# LilyPad_Arduino_SimpleSnap.net
KiCad netlist of a schematic drawn in EAGLE
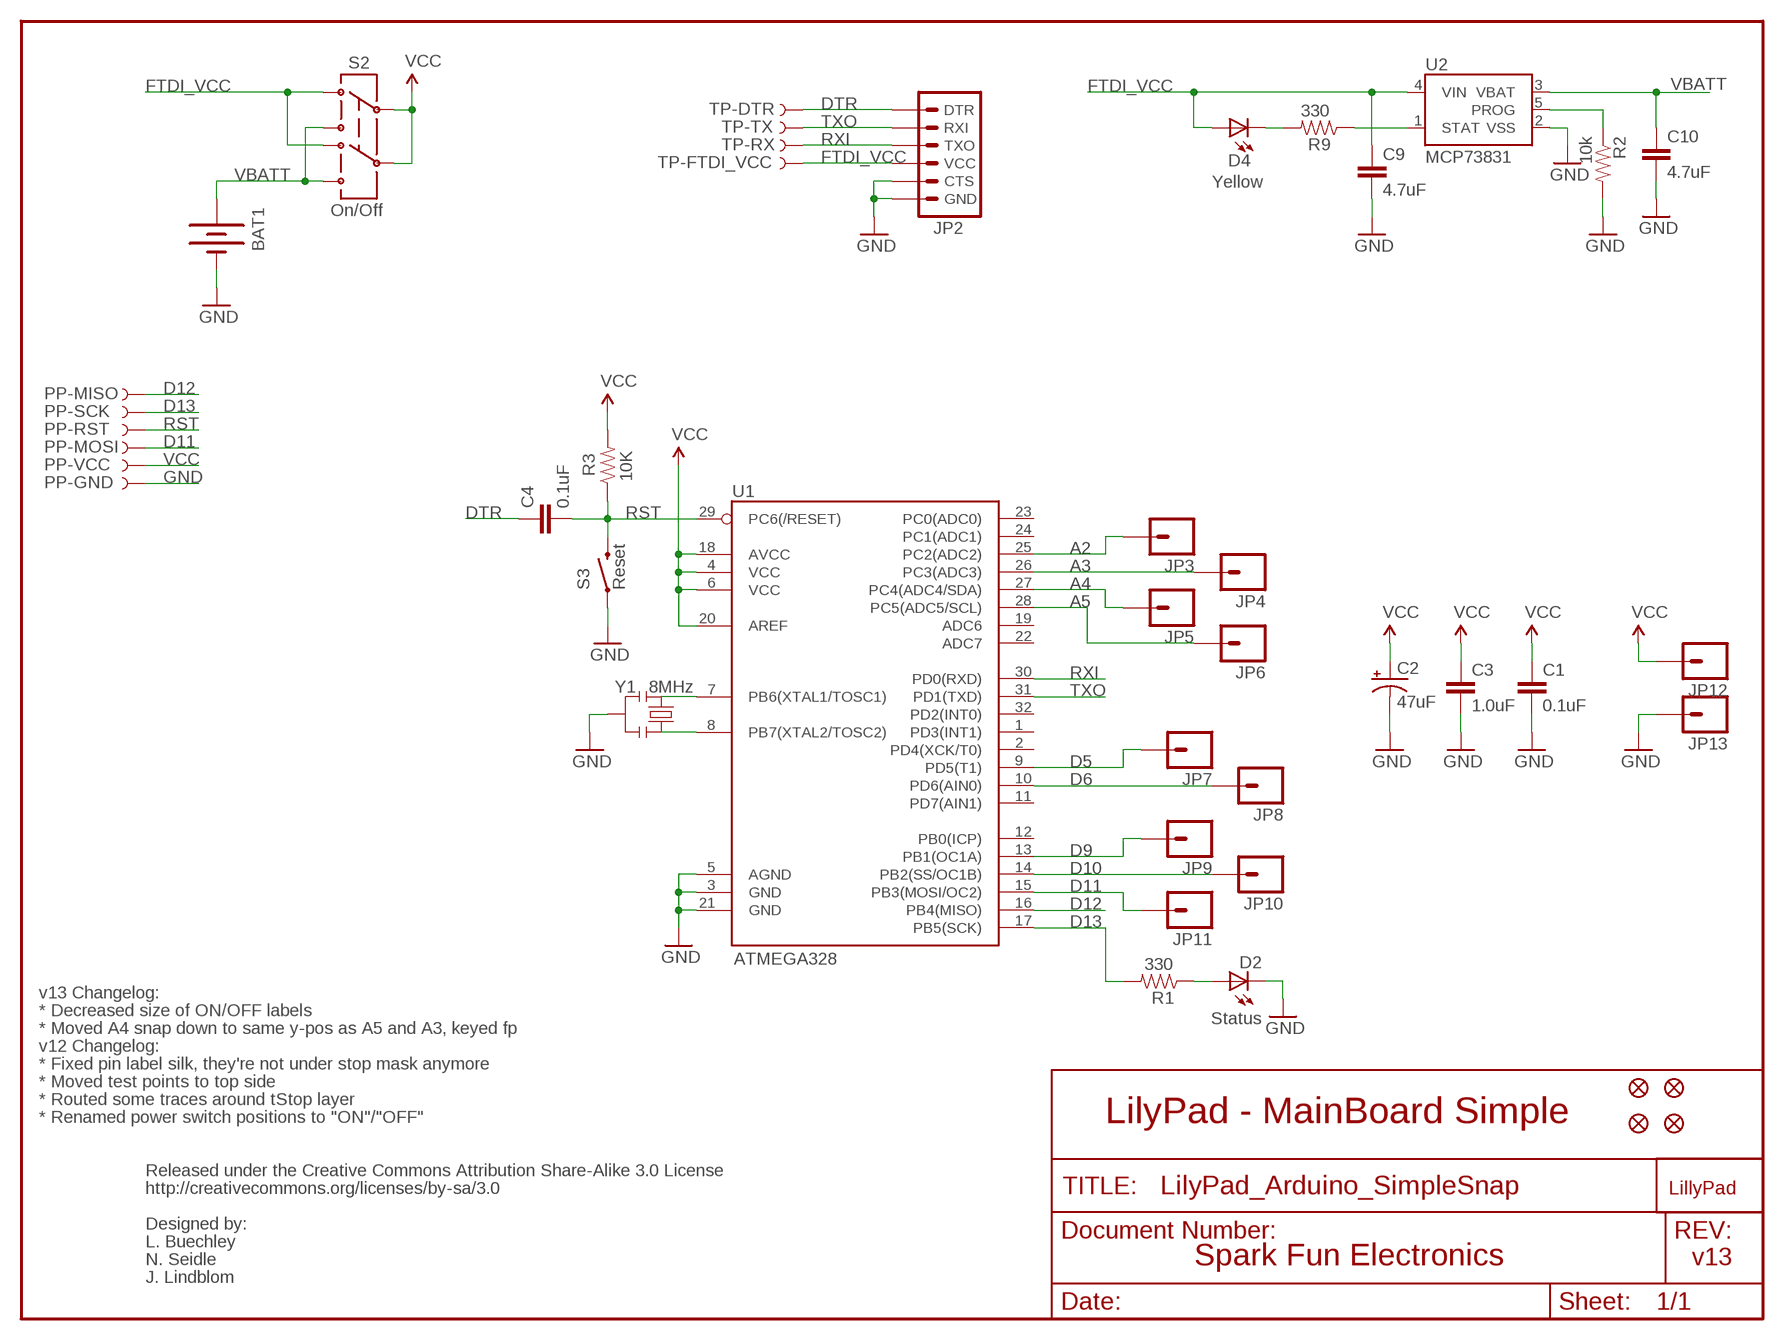
[diagram p0: schematic, sheet 1]

(export (version "E")
  (design (tool "Eeschema 10.0.6"))
  (components
    (comp (ref "BAT1")
      (value "BATTERY110-TABS")
      (footprint "eagle-import:LIPO-110-TABS")
      (libsource (lib "eagle-import") (part "BATTERY110-TABS"))
    )
    (comp (ref "C1")
      (value "0.1uF")
      (footprint "eagle-import:0402-CAP")
      (libsource (lib "eagle-import") (part "CAP0402-CAP"))
    )
    (comp (ref "C2")
      (value "47uF")
      (footprint "eagle-import:EIA3528")
      (libsource (lib "eagle-import") (part "CAP_POL3528"))
    )
    (comp (ref "C3")
      (value "1.0uF")
      (footprint "eagle-import:0402-CAP")
      (libsource (lib "eagle-import") (part "CAP0402-CAP"))
    )
    (comp (ref "C4")
      (value "0.1uF")
      (footprint "eagle-import:0402-CAP")
      (libsource (lib "eagle-import") (part "CAP0402-CAP"))
    )
    (comp (ref "C9")
      (value "4.7uF")
      (footprint "eagle-import:0402-CAP")
      (libsource (lib "eagle-import") (part "CAP0402-CAP"))
    )
    (comp (ref "C10")
      (value "4.7uF")
      (footprint "eagle-import:0402-CAP")
      (libsource (lib "eagle-import") (part "CAP0402-CAP"))
    )
    (comp (ref "D2")
      (value "Status")
      (footprint "eagle-import:LED-0603")
      (libsource (lib "eagle-import") (part "LED0603"))
    )
    (comp (ref "D4")
      (value "Yellow")
      (footprint "eagle-import:LED-0603")
      (libsource (lib "eagle-import") (part "LED0603"))
    )
    (comp (ref "JP1")
      (value "FIDUCIALUFIDUCIAL")
      (footprint "eagle-import:MICRO-FIDUCIAL")
      (libsource (lib "eagle-import") (part "FIDUCIALUFIDUCIAL"))
    )
    (comp (ref "JP2")
      (value "ARDUINO_SERIAL_PROGRAMSMD")
      (footprint "eagle-import:1X06-SMD")
      (libsource (lib "eagle-import") (part "ARDUINO_SERIAL_PROGRAMSMD"))
    )
    (comp (ref "JP3")
      (value "M01SNAP-FEMALE_LARGE")
      (footprint "eagle-import:SNAP-FEMALE")
      (libsource (lib "eagle-import") (part "M01SNAP-FEMALE"))
    )
    (comp (ref "JP4")
      (value "M01SNAP-FEMALE_LARGE")
      (footprint "eagle-import:SNAP-FEMALE")
      (libsource (lib "eagle-import") (part "M01SNAP-FEMALE"))
    )
    (comp (ref "JP5")
      (value "M01SNAP-FEMALE_LARGE")
      (footprint "eagle-import:SNAP-FEMALE")
      (libsource (lib "eagle-import") (part "M01SNAP-FEMALE"))
    )
    (comp (ref "JP6")
      (value "M01SNAP-FEMALE_LARGE")
      (footprint "eagle-import:SNAP-FEMALE")
      (libsource (lib "eagle-import") (part "M01SNAP-FEMALE"))
    )
    (comp (ref "JP7")
      (value "M01SNAP-FEMALE_LARGE")
      (footprint "eagle-import:SNAP-FEMALE")
      (libsource (lib "eagle-import") (part "M01SNAP-FEMALE"))
    )
    (comp (ref "JP8")
      (value "M01SNAP-FEMALE_LARGE")
      (footprint "eagle-import:SNAP-FEMALE")
      (libsource (lib "eagle-import") (part "M01SNAP-FEMALE"))
    )
    (comp (ref "JP9")
      (value "M01SNAP-FEMALE_LARGE")
      (footprint "eagle-import:SNAP-FEMALE")
      (libsource (lib "eagle-import") (part "M01SNAP-FEMALE"))
    )
    (comp (ref "JP10")
      (value "M01SNAP-FEMALE_LARGE")
      (footprint "eagle-import:SNAP-FEMALE")
      (libsource (lib "eagle-import") (part "M01SNAP-FEMALE"))
    )
    (comp (ref "JP11")
      (value "M01SNAP-FEMALE_LARGE")
      (footprint "eagle-import:SNAP-FEMALE")
      (libsource (lib "eagle-import") (part "M01SNAP-FEMALE"))
    )
    (comp (ref "JP12")
      (value "M01SNAP-FEMALE_LARGE")
      (footprint "eagle-import:SNAP-FEMALE")
      (libsource (lib "eagle-import") (part "M01SNAP-FEMALE"))
    )
    (comp (ref "JP13")
      (value "M01SNAP-FEMALE_LARGE")
      (footprint "eagle-import:SNAP-FEMALE")
      (libsource (lib "eagle-import") (part "M01SNAP-FEMALE"))
    )
    (comp (ref "JP14")
      (value "FIDUCIALUFIDUCIAL")
      (footprint "eagle-import:MICRO-FIDUCIAL")
      (libsource (lib "eagle-import") (part "FIDUCIALUFIDUCIAL"))
    )
    (comp (ref "JP15")
      (value "FIDUCIALUFIDUCIAL")
      (footprint "eagle-import:MICRO-FIDUCIAL")
      (libsource (lib "eagle-import") (part "FIDUCIALUFIDUCIAL"))
    )
    (comp (ref "JP16")
      (value "FIDUCIALUFIDUCIAL")
      (footprint "eagle-import:MICRO-FIDUCIAL")
      (libsource (lib "eagle-import") (part "FIDUCIALUFIDUCIAL"))
    )
    (comp (ref "PP-GND")
      (value "TEST-POINT3X5")
      (footprint "eagle-import:PAD.03X.05")
      (libsource (lib "eagle-import") (part "TEST-POINT3X5"))
    )
    (comp (ref "PP-MISO")
      (value "TEST-POINT3X5")
      (footprint "eagle-import:PAD.03X.05")
      (libsource (lib "eagle-import") (part "TEST-POINT3X5"))
    )
    (comp (ref "PP-MOSI")
      (value "TEST-POINT3X5")
      (footprint "eagle-import:PAD.03X.05")
      (libsource (lib "eagle-import") (part "TEST-POINT3X5"))
    )
    (comp (ref "PP-RST")
      (value "TEST-POINT3X5")
      (footprint "eagle-import:PAD.03X.05")
      (libsource (lib "eagle-import") (part "TEST-POINT3X5"))
    )
    (comp (ref "PP-SCK")
      (value "TEST-POINT3X5")
      (footprint "eagle-import:PAD.03X.05")
      (libsource (lib "eagle-import") (part "TEST-POINT3X5"))
    )
    (comp (ref "PP-VCC")
      (value "TEST-POINT3X5")
      (footprint "eagle-import:PAD.03X.05")
      (libsource (lib "eagle-import") (part "TEST-POINT3X5"))
    )
    (comp (ref "R1")
      (value "330")
      (footprint "eagle-import:0402-RES")
      (libsource (lib "eagle-import") (part "RESISTOR0402-RES"))
    )
    (comp (ref "R2")
      (value "10k")
      (footprint "eagle-import:0402-RES")
      (libsource (lib "eagle-import") (part "RESISTOR0402-RES"))
    )
    (comp (ref "R3")
      (value "10K")
      (footprint "eagle-import:0402-RES")
      (libsource (lib "eagle-import") (part "RESISTOR0402-RES"))
    )
    (comp (ref "R9")
      (value "330")
      (footprint "eagle-import:0402-RES")
      (libsource (lib "eagle-import") (part "RESISTOR0402-RES"))
    )
    (comp (ref "S2")
      (value "On/Off")
      (footprint "eagle-import:AYZ0202")
      (libsource (lib "eagle-import") (part "AYZ0202"))
    )
    (comp (ref "S3")
      (value "Reset")
      (footprint "eagle-import:TACTILE_SWITCH_SMD")
      (libsource (lib "eagle-import") (part "SWITCH-MOMENTARY-2SMD"))
    )
    (comp (ref "TP-DTR")
      (value "TEST-POINT3X5")
      (footprint "eagle-import:PAD.03X.05")
      (libsource (lib "eagle-import") (part "TEST-POINT3X5"))
    )
    (comp (ref "TP-FTDI_VCC")
      (value "TEST-POINT3X5")
      (footprint "eagle-import:PAD.03X.05")
      (libsource (lib "eagle-import") (part "TEST-POINT3X5"))
    )
    (comp (ref "TP-RX")
      (value "TEST-POINT3X5")
      (footprint "eagle-import:PAD.03X.05")
      (libsource (lib "eagle-import") (part "TEST-POINT3X5"))
    )
    (comp (ref "TP-TX")
      (value "TEST-POINT3X5")
      (footprint "eagle-import:PAD.03X.05")
      (libsource (lib "eagle-import") (part "TEST-POINT3X5"))
    )
    (comp (ref "U$2")
      (value "LOGO-LPLP")
      (footprint "eagle-import:LOGO-LILYPAD")
      (libsource (lib "eagle-import") (part "LOGO-LPLP"))
    )
    (comp (ref "U1")
      (value "ATMEGA328")
      (footprint "eagle-import:TQFP32-08")
      (libsource (lib "eagle-import") (part "ATMEGA168"))
    )
    (comp (ref "U2")
      (value "MCP73831")
      (footprint "eagle-import:SOT23-5")
      (libsource (lib "eagle-import") (part "MCP73831"))
    )
    (comp (ref "Y1")
      (value "8MHz")
      (footprint "eagle-import:RESONATOR-SMD")
      (libsource (lib "eagle-import") (part "RESONATORSMD"))
    )
  )
  (nets
    (net (code "1") (name "/A2") (class "Default")
      (node (ref "JP3") (pin "1") (pinfunction "1_1") (pintype "passive"))
      (node (ref "U1") (pin "25") (pinfunction "PC2(ADC2)_25") (pintype "bidirectional"))
    )
    (net (code "2") (name "/A3") (class "Default")
      (node (ref "JP4") (pin "1") (pinfunction "1_1") (pintype "passive"))
      (node (ref "U1") (pin "26") (pinfunction "PC3(ADC3)_26") (pintype "bidirectional"))
    )
    (net (code "3") (name "/A4") (class "Default")
      (node (ref "JP5") (pin "1") (pinfunction "1_1") (pintype "passive"))
      (node (ref "U1") (pin "27") (pinfunction "PC4(ADC4/SDA)_27") (pintype "bidirectional"))
    )
    (net (code "4") (name "/A5") (class "Default")
      (node (ref "JP6") (pin "1") (pinfunction "1_1") (pintype "passive"))
      (node (ref "U1") (pin "28") (pinfunction "PC5(ADC5/SCL)_28") (pintype "bidirectional"))
    )
    (net (code "5") (name "/D5") (class "Default")
      (node (ref "JP7") (pin "1") (pinfunction "1_1") (pintype "passive"))
      (node (ref "U1") (pin "9") (pinfunction "PD5(T1)_9") (pintype "bidirectional"))
    )
    (net (code "6") (name "/D6") (class "Default")
      (node (ref "JP8") (pin "1") (pinfunction "1_1") (pintype "passive"))
      (node (ref "U1") (pin "10") (pinfunction "PD6(AIN0)_10") (pintype "bidirectional"))
    )
    (net (code "7") (name "/D9") (class "Default")
      (node (ref "JP9") (pin "1") (pinfunction "1_1") (pintype "passive"))
      (node (ref "U1") (pin "13") (pinfunction "PB1(OC1A)_13") (pintype "bidirectional"))
    )
    (net (code "8") (name "/D10") (class "Default")
      (node (ref "JP10") (pin "1") (pinfunction "1_1") (pintype "passive"))
      (node (ref "U1") (pin "14") (pinfunction "PB2(SS/OC1B)_14") (pintype "bidirectional"))
    )
    (net (code "9") (name "/D11") (class "Default")
      (node (ref "JP11") (pin "1") (pinfunction "1_1") (pintype "passive"))
      (node (ref "PP-MOSI") (pin "P$1") (pinfunction "1_P$1") (pintype "bidirectional"))
      (node (ref "U1") (pin "15") (pinfunction "PB3(MOSI/OC2)_15") (pintype "bidirectional"))
    )
    (net (code "10") (name "/D12") (class "Default")
      (node (ref "PP-MISO") (pin "P$1") (pinfunction "1_P$1") (pintype "bidirectional"))
      (node (ref "U1") (pin "16") (pinfunction "PB4(MISO)_16") (pintype "bidirectional"))
    )
    (net (code "11") (name "/D13") (class "Default")
      (node (ref "PP-SCK") (pin "P$1") (pinfunction "1_P$1") (pintype "bidirectional"))
      (node (ref "R1") (pin "2") (pinfunction "2_2") (pintype "passive"))
      (node (ref "U1") (pin "17") (pinfunction "PB5(SCK)_17") (pintype "bidirectional"))
    )
    (net (code "12") (name "/DTR") (class "Default")
      (node (ref "C4") (pin "1") (pinfunction "1_1") (pintype "passive"))
      (node (ref "JP2") (pin "1") (pinfunction "DTR_1") (pintype "passive"))
      (node (ref "TP-DTR") (pin "P$1") (pinfunction "1_P$1") (pintype "bidirectional"))
    )
    (net (code "13") (name "/FTDI_VCC") (class "Default")
      (node (ref "C9") (pin "1") (pinfunction "1_1") (pintype "passive"))
      (node (ref "D4") (pin "A") (pinfunction "A_A") (pintype "passive"))
      (node (ref "JP2") (pin "4") (pinfunction "VCC_4") (pintype "passive"))
      (node (ref "S2") (pin "3") (pinfunction "1_3") (pintype "bidirectional"))
      (node (ref "S2") (pin "6") (pinfunction "4_6") (pintype "bidirectional"))
      (node (ref "TP-FTDI_VCC") (pin "P$1") (pinfunction "1_P$1") (pintype "bidirectional"))
      (node (ref "U2") (pin "4") (pinfunction "VIN_4") (pintype "power_in"))
    )
    (net (code "14") (name "/RST") (class "Default")
      (node (ref "C4") (pin "2") (pinfunction "2_2") (pintype "passive"))
      (node (ref "PP-RST") (pin "P$1") (pinfunction "1_P$1") (pintype "bidirectional"))
      (node (ref "R3") (pin "1") (pinfunction "1_1") (pintype "passive"))
      (node (ref "S3") (pin "3") (pinfunction "2_3") (pintype "passive"))
      (node (ref "U1") (pin "29") (pinfunction "PC6(/RESET)_29") (pintype "bidirectional"))
    )
    (net (code "15") (name "/RXI") (class "Default")
      (node (ref "JP2") (pin "3") (pinfunction "TXO_3") (pintype "passive"))
      (node (ref "TP-RX") (pin "P$1") (pinfunction "1_P$1") (pintype "bidirectional"))
      (node (ref "U1") (pin "30") (pinfunction "PD0(RXD)_30") (pintype "bidirectional"))
    )
    (net (code "16") (name "/TXO") (class "Default")
      (node (ref "JP2") (pin "2") (pinfunction "RXI_2") (pintype "passive"))
      (node (ref "TP-TX") (pin "P$1") (pinfunction "1_P$1") (pintype "bidirectional"))
      (node (ref "U1") (pin "31") (pinfunction "PD1(TXD)_31") (pintype "bidirectional"))
    )
    (net (code "17") (name "/VBATT") (class "Default")
      (node (ref "BAT1") (pin "+") (pinfunction "+_+") (pintype "power_in"))
      (node (ref "C10") (pin "1") (pinfunction "1_1") (pintype "passive"))
      (node (ref "S2") (pin "1") (pinfunction "3_1") (pintype "bidirectional"))
      (node (ref "S2") (pin "4") (pinfunction "6_4") (pintype "bidirectional"))
      (node (ref "U2") (pin "3") (pinfunction "VBAT_3") (pintype "power_in"))
    )
    (net (code "18") (name "GND") (class "Default")
      (node (ref "BAT1") (pin "-") (pinfunction "-_-") (pintype "power_in"))
      (node (ref "C1") (pin "2") (pinfunction "2_2") (pintype "passive"))
      (node (ref "C10") (pin "2") (pinfunction "2_2") (pintype "passive"))
      (node (ref "C2") (pin "C") (pinfunction "-_C") (pintype "passive"))
      (node (ref "C3") (pin "2") (pinfunction "2_2") (pintype "passive"))
      (node (ref "C9") (pin "2") (pinfunction "2_2") (pintype "passive"))
      (node (ref "D2") (pin "C") (pinfunction "C_C") (pintype "passive"))
      (node (ref "JP13") (pin "1") (pinfunction "1_1") (pintype "passive"))
      (node (ref "JP2") (pin "5") (pinfunction "CTS_5") (pintype "passive"))
      (node (ref "JP2") (pin "6") (pinfunction "GND_6") (pintype "passive"))
      (node (ref "PP-GND") (pin "P$1") (pinfunction "1_P$1") (pintype "bidirectional"))
      (node (ref "R2") (pin "2") (pinfunction "2_2") (pintype "passive"))
      (node (ref "S3") (pin "1") (pinfunction "1_1") (pintype "passive"))
      (node (ref "U1") (pin "21") (pinfunction "GND_21") (pintype "bidirectional"))
      (node (ref "U1") (pin "3") (pinfunction "GND_3") (pintype "bidirectional"))
      (node (ref "U1") (pin "5") (pinfunction "AGND_5") (pintype "bidirectional"))
      (node (ref "U2") (pin "2") (pinfunction "VSS_2") (pintype "power_in"))
      (node (ref "Y1") (pin "2") (pinfunction "2_2") (pintype "passive"))
    )
    (net (code "19") (name "Net-(D2-PadA)") (class "Default")
      (node (ref "D2") (pin "A") (pinfunction "A_A") (pintype "passive"))
      (node (ref "R1") (pin "1") (pinfunction "1_1") (pintype "passive"))
    )
    (net (code "20") (name "Net-(D4-PadC)") (class "Default")
      (node (ref "D4") (pin "C") (pinfunction "C_C") (pintype "passive"))
      (node (ref "R9") (pin "2") (pinfunction "2_2") (pintype "passive"))
    )
    (net (code "21") (name "Net-(U1-PB6(XTAL1{slash}TOSC1))") (class "Default")
      (node (ref "U1") (pin "7") (pinfunction "PB6(XTAL1/TOSC1)_7") (pintype "bidirectional"))
      (node (ref "Y1") (pin "1") (pinfunction "1_1") (pintype "passive"))
    )
    (net (code "22") (name "Net-(U1-PB7(XTAL2{slash}TOSC2))") (class "Default")
      (node (ref "U1") (pin "8") (pinfunction "PB7(XTAL2/TOSC2)_8") (pintype "bidirectional"))
      (node (ref "Y1") (pin "3") (pinfunction "3_3") (pintype "passive"))
    )
    (net (code "23") (name "Net-(U2-PROG)") (class "Default")
      (node (ref "R2") (pin "1") (pinfunction "1_1") (pintype "passive"))
      (node (ref "U2") (pin "5") (pinfunction "PROG_5") (pintype "input"))
    )
    (net (code "24") (name "Net-(U2-STAT)") (class "Default")
      (node (ref "R9") (pin "1") (pinfunction "1_1") (pintype "passive"))
      (node (ref "U2") (pin "1") (pinfunction "STAT_1") (pintype "output"))
    )
    (net (code "25") (name "VCC") (class "Default")
      (node (ref "C1") (pin "1") (pinfunction "1_1") (pintype "passive"))
      (node (ref "C2") (pin "A") (pinfunction "+_A") (pintype "passive"))
      (node (ref "C3") (pin "1") (pinfunction "1_1") (pintype "passive"))
      (node (ref "JP12") (pin "1") (pinfunction "1_1") (pintype "passive"))
      (node (ref "PP-VCC") (pin "P$1") (pinfunction "1_P$1") (pintype "bidirectional"))
      (node (ref "R3") (pin "2") (pinfunction "2_2") (pintype "passive"))
      (node (ref "S2") (pin "2") (pinfunction "2_2") (pintype "bidirectional"))
      (node (ref "S2") (pin "5") (pinfunction "5_5") (pintype "bidirectional"))
      (node (ref "U1") (pin "18") (pinfunction "AVCC_18") (pintype "bidirectional"))
      (node (ref "U1") (pin "20") (pinfunction "AREF_20") (pintype "bidirectional"))
      (node (ref "U1") (pin "4") (pinfunction "VCC_4") (pintype "bidirectional"))
      (node (ref "U1") (pin "6") (pinfunction "VCC_6") (pintype "bidirectional"))
    )
    (net (code "26") (name "unconnected-(U1-ADC6-Pad19)") (class "Default")
      (node (ref "U1") (pin "19") (pinfunction "ADC6_19") (pintype "bidirectional"))
    )
    (net (code "27") (name "unconnected-(U1-ADC7-Pad22)") (class "Default")
      (node (ref "U1") (pin "22") (pinfunction "ADC7_22") (pintype "bidirectional"))
    )
    (net (code "28") (name "unconnected-(U1-PB0(ICP)-Pad12)") (class "Default")
      (node (ref "U1") (pin "12") (pinfunction "PB0(ICP)_12") (pintype "bidirectional"))
    )
    (net (code "29") (name "unconnected-(U1-PC0(ADC0)-Pad23)") (class "Default")
      (node (ref "U1") (pin "23") (pinfunction "PC0(ADC0)_23") (pintype "bidirectional"))
    )
    (net (code "30") (name "unconnected-(U1-PC1(ADC1)-Pad24)") (class "Default")
      (node (ref "U1") (pin "24") (pinfunction "PC1(ADC1)_24") (pintype "bidirectional"))
    )
    (net (code "31") (name "unconnected-(U1-PD2(INT0)-Pad32)") (class "Default")
      (node (ref "U1") (pin "32") (pinfunction "PD2(INT0)_32") (pintype "bidirectional"))
    )
    (net (code "32") (name "unconnected-(U1-PD3(INT1)-Pad1)") (class "Default")
      (node (ref "U1") (pin "1") (pinfunction "PD3(INT1)_1") (pintype "bidirectional"))
    )
    (net (code "33") (name "unconnected-(U1-PD4(XCK{slash}T0)-Pad2)") (class "Default")
      (node (ref "U1") (pin "2") (pinfunction "PD4(XCK/T0)_2") (pintype "bidirectional"))
    )
    (net (code "34") (name "unconnected-(U1-PD7(AIN1)-Pad11)") (class "Default")
      (node (ref "U1") (pin "11") (pinfunction "PD7(AIN1)_11") (pintype "bidirectional"))
    )
  )
)
